# astabil_multivibrator.net
KiCad netlist of a schematic drawn in EAGLE
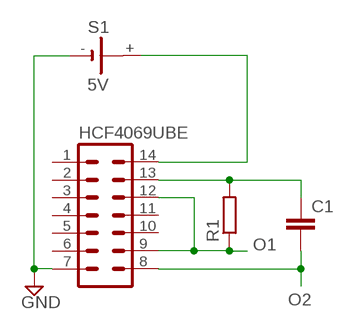
[diagram p0: schematic, sheet 1]

(export (version "E")
  (design (tool "Eeschema 10.0.6"))
  (components
    (comp (ref "C1")
      (value "C-EU025-024X044")
      (footprint "eagle-import:C025-024X044")
      (libsource (lib "eagle-import") (part "C-EU025-024X044"))
    )
    (comp (ref "HCF4069UBE")
      (value "IC14P")
      (footprint "eagle-import:IC14P")
      (libsource (lib "eagle-import") (part "IC14P"))
    )
    (comp (ref "R1")
      (value "R-EU_0204/2V")
      (footprint "eagle-import:0204V")
      (libsource (lib "eagle-import") (part "R-EU_0204/2V"))
    )
    (comp (ref "S1")
      (value "5V")
      (footprint "eagle-import:1V60R")
      (libsource (lib "eagle-import") (part "1V60R"))
    )
  )
  (nets
    (net (code "1") (name "GND") (class "Default")
      (node (ref "HCF4069UBE") (pin "7") (pinfunction "7_7") (pintype "passive"))
      (node (ref "S1") (pin "-") (pinfunction "-_-") (pintype "passive"))
    )
    (net (code "2") (name "Net-(C1-Pad1)") (class "Default")
      (node (ref "C1") (pin "1") (pinfunction "1_1") (pintype "passive"))
      (node (ref "HCF4069UBE") (pin "13") (pinfunction "13_13") (pintype "passive"))
      (node (ref "R1") (pin "2") (pinfunction "2_2") (pintype "passive"))
    )
    (net (code "3") (name "Net-(C1-Pad2)") (class "Default")
      (node (ref "C1") (pin "2") (pinfunction "2_2") (pintype "passive"))
      (node (ref "HCF4069UBE") (pin "8") (pinfunction "8_8") (pintype "passive"))
    )
    (net (code "4") (name "Net-(HCF4069UBE-Pad12)") (class "Default")
      (node (ref "HCF4069UBE") (pin "12") (pinfunction "12_12") (pintype "passive"))
      (node (ref "HCF4069UBE") (pin "9") (pinfunction "9_9") (pintype "passive"))
      (node (ref "R1") (pin "1") (pinfunction "1_1") (pintype "passive"))
    )
    (net (code "5") (name "Net-(HCF4069UBE-Pad14)") (class "Default")
      (node (ref "HCF4069UBE") (pin "14") (pinfunction "14_14") (pintype "passive"))
      (node (ref "S1") (pin "+") (pinfunction "+_+") (pintype "passive"))
    )
    (net (code "6") (name "unconnected-(HCF4069UBE-Pad1)") (class "Default")
      (node (ref "HCF4069UBE") (pin "1") (pinfunction "1_1") (pintype "passive"))
    )
    (net (code "7") (name "unconnected-(HCF4069UBE-Pad2)") (class "Default")
      (node (ref "HCF4069UBE") (pin "2") (pinfunction "2_2") (pintype "passive"))
    )
    (net (code "8") (name "unconnected-(HCF4069UBE-Pad3)") (class "Default")
      (node (ref "HCF4069UBE") (pin "3") (pinfunction "3_3") (pintype "passive"))
    )
    (net (code "9") (name "unconnected-(HCF4069UBE-Pad4)") (class "Default")
      (node (ref "HCF4069UBE") (pin "4") (pinfunction "4_4") (pintype "passive"))
    )
    (net (code "10") (name "unconnected-(HCF4069UBE-Pad5)") (class "Default")
      (node (ref "HCF4069UBE") (pin "5") (pinfunction "5_5") (pintype "passive"))
    )
    (net (code "11") (name "unconnected-(HCF4069UBE-Pad6)") (class "Default")
      (node (ref "HCF4069UBE") (pin "6") (pinfunction "6_6") (pintype "passive"))
    )
    (net (code "12") (name "unconnected-(HCF4069UBE-Pad10)") (class "Default")
      (node (ref "HCF4069UBE") (pin "10") (pinfunction "10_10") (pintype "passive"))
    )
    (net (code "13") (name "unconnected-(HCF4069UBE-Pad11)") (class "Default")
      (node (ref "HCF4069UBE") (pin "11") (pinfunction "11_11") (pintype "passive"))
    )
    (net (code "14") (name "unconnected-(S1-+-Pad+@1)") (class "Default")
      (node (ref "S1") (pin "+@1") (pinfunction "+_+@1") (pintype "passive"))
    )
  )
)
